# v0_1.net
KiCad netlist of a schematic drawn in EAGLE
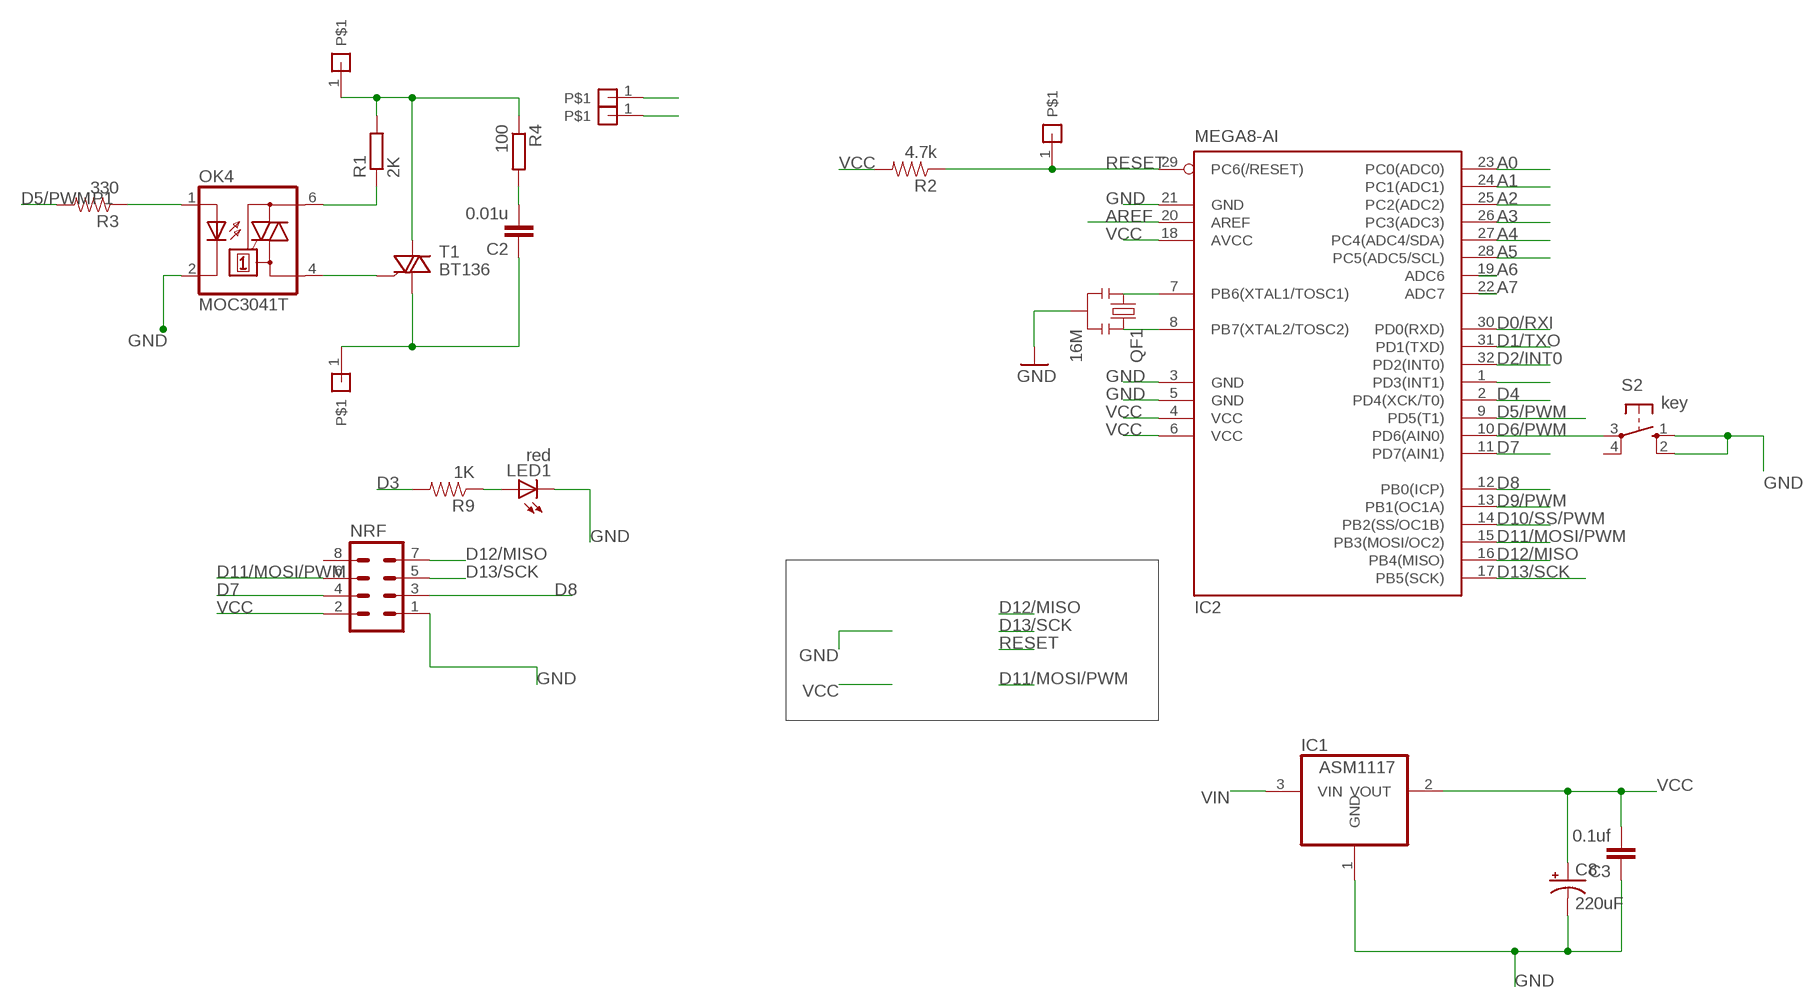
[diagram p0: schematic, sheet 1]

(export (version "E")
  (design (tool "Eeschema 10.0.6"))
  (components
    (comp (ref "C2")
      (value "0.01u")
      (footprint "eagle-import:C050-024X044")
      (libsource (lib "eagle-import") (part "C-EU050-024X044"))
    )
    (comp (ref "C3")
      (value "0.1uf")
      (footprint "eagle-import:0603-CAP")
      (libsource (lib "eagle-import") (part "CAP0603-CAP"))
    )
    (comp (ref "C8")
      (value "220uF")
      (footprint "eagle-import:EIA3528")
      (libsource (lib "eagle-import") (part "CAP_POL3528"))
    )
    (comp (ref "IC1")
      (value "ASM1117")
      (footprint "eagle-import:SOT223")
      (fields (field (name "MPN") "REG1117"))
      (libsource (lib "eagle-import") (part "REG1117"))
    )
    (comp (ref "IC2")
      (value "MEGA8-AI")
      (footprint "eagle-import:TQFP32-08")
      (fields (field (name "MPN") "ATMEGA8-16AU"))
      (libsource (lib "eagle-import") (part "MEGA8-AI"))
    )
    (comp (ref "LED1")
      (value "red")
      (footprint "eagle-import:LED3MM")
      (libsource (lib "eagle-import") (part "LED3MM"))
    )
    (comp (ref "NRF")
      (value "MA04-2")
      (footprint "eagle-import:MA04-2")
      (libsource (lib "eagle-import") (part "MA04-2"))
    )
    (comp (ref "OK4")
      (value "MOC3041T")
      (footprint "eagle-import:DIL06B")
      (libsource (lib "eagle-import") (part "MOC30T41"))
    )
    (comp (ref "QF1")
      (value "16M")
      (footprint "eagle-import:RESONATOR-PTH")
      (libsource (lib "eagle-import") (part "RESONATORPTH"))
    )
    (comp (ref "R1")
      (value "2K")
      (footprint "eagle-import:0204_7")
      (libsource (lib "eagle-import") (part "R-EU_0204/7"))
    )
    (comp (ref "R2")
      (value "4.7k")
      (footprint "eagle-import:0603-RES")
      (libsource (lib "eagle-import") (part "RESISTOR0603-RES"))
    )
    (comp (ref "R3")
      (value "330")
      (footprint "eagle-import:0603-RES")
      (libsource (lib "eagle-import") (part "RESISTOR0603-RES"))
    )
    (comp (ref "R4")
      (value "100")
      (footprint "eagle-import:0204_7")
      (libsource (lib "eagle-import") (part "R-EU_0204/7"))
    )
    (comp (ref "R9")
      (value "1K")
      (footprint "eagle-import:0603-RES")
      (libsource (lib "eagle-import") (part "RESISTOR0603-RES"))
    )
    (comp (ref "S2")
      (value "key")
      (footprint "eagle-import:B3F-10XX")
      (fields
        (field (name "MPN") "B3F-1000")
        (field (name "MPN_1") "B3F-1000")
        (field (name "OC_FARNELL") "176432")
        (field (name "OC_NEWARK") "36M3542")
      )
      (libsource (lib "eagle-import") (part "10-XX"))
    )
    (comp (ref "T1")
      (value "BT136")
      (footprint "eagle-import:TO220AB")
      (libsource (lib "eagle-import") (part "BT136"))
    )
    (comp (ref "U$1")
      (value "PIN1")
      (footprint "eagle-import:PIN1")
      (libsource (lib "eagle-import") (part "PIN1"))
    )
    (comp (ref "U$2")
      (value "PIN1")
      (footprint "eagle-import:PIN1")
      (libsource (lib "eagle-import") (part "PIN1"))
    )
    (comp (ref "U$3")
      (value "PIN1")
      (footprint "eagle-import:PIN1")
      (libsource (lib "eagle-import") (part "PIN1"))
    )
    (comp (ref "U$4")
      (value "PIN1")
      (footprint "eagle-import:PIN1")
      (libsource (lib "eagle-import") (part "PIN1"))
    )
    (comp (ref "U$5")
      (value "PIN1")
      (footprint "eagle-import:PIN1")
      (libsource (lib "eagle-import") (part "PIN1"))
    )
  )
  (nets
    (net (code "1") (name "/A0") (class "Default")
      (node (ref "IC2") (pin "23") (pinfunction "PC0(ADC0)_23") (pintype "bidirectional"))
    )
    (net (code "2") (name "/A1") (class "Default")
      (node (ref "IC2") (pin "24") (pinfunction "PC1(ADC1)_24") (pintype "bidirectional"))
    )
    (net (code "3") (name "/A2") (class "Default")
      (node (ref "IC2") (pin "25") (pinfunction "PC2(ADC2)_25") (pintype "bidirectional"))
    )
    (net (code "4") (name "/A3") (class "Default")
      (node (ref "IC2") (pin "26") (pinfunction "PC3(ADC3)_26") (pintype "bidirectional"))
    )
    (net (code "5") (name "/A4") (class "Default")
      (node (ref "IC2") (pin "27") (pinfunction "PC4(ADC4/SDA)_27") (pintype "bidirectional"))
    )
    (net (code "6") (name "/A5") (class "Default")
      (node (ref "IC2") (pin "28") (pinfunction "PC5(ADC5/SCL)_28") (pintype "bidirectional"))
    )
    (net (code "7") (name "/A6") (class "Default")
      (node (ref "IC2") (pin "19") (pinfunction "ADC6_19") (pintype "bidirectional"))
    )
    (net (code "8") (name "/A7") (class "Default")
      (node (ref "IC2") (pin "22") (pinfunction "ADC7_22") (pintype "bidirectional"))
    )
    (net (code "9") (name "/AREF") (class "Default")
      (node (ref "IC2") (pin "20") (pinfunction "AREF_20") (pintype "passive"))
    )
    (net (code "10") (name "/D0{slash}RXI") (class "Default")
      (node (ref "IC2") (pin "30") (pinfunction "PD0(RXD)_30") (pintype "bidirectional"))
    )
    (net (code "11") (name "/D1{slash}TXO") (class "Default")
      (node (ref "IC2") (pin "31") (pinfunction "PD1(TXD)_31") (pintype "bidirectional"))
    )
    (net (code "12") (name "/D2{slash}INT0") (class "Default")
      (node (ref "IC2") (pin "32") (pinfunction "PD2(INT0)_32") (pintype "bidirectional"))
    )
    (net (code "13") (name "/D3") (class "Default")
      (node (ref "IC2") (pin "1") (pinfunction "PD3(INT1)_1") (pintype "bidirectional"))
      (node (ref "R9") (pin "2") (pinfunction "2_2") (pintype "passive"))
    )
    (net (code "14") (name "/D4") (class "Default")
      (node (ref "IC2") (pin "2") (pinfunction "PD4(XCK/T0)_2") (pintype "bidirectional"))
    )
    (net (code "15") (name "/D5{slash}PWM") (class "Default")
      (node (ref "IC2") (pin "9") (pinfunction "PD5(T1)_9") (pintype "bidirectional"))
      (node (ref "R3") (pin "2") (pinfunction "2_2") (pintype "passive"))
    )
    (net (code "16") (name "/D6{slash}PWM") (class "Default")
      (node (ref "IC2") (pin "10") (pinfunction "PD6(AIN0)_10") (pintype "bidirectional"))
      (node (ref "S2") (pin "3") (pinfunction "P_3") (pintype "passive"))
    )
    (net (code "17") (name "/D7") (class "Default")
      (node (ref "IC2") (pin "11") (pinfunction "PD7(AIN1)_11") (pintype "bidirectional"))
      (node (ref "NRF") (pin "4") (pinfunction "4_4") (pintype "passive"))
    )
    (net (code "18") (name "/D8") (class "Default")
      (node (ref "IC2") (pin "12") (pinfunction "PB0(ICP)_12") (pintype "bidirectional"))
      (node (ref "NRF") (pin "3") (pinfunction "3_3") (pintype "passive"))
    )
    (net (code "19") (name "/D9{slash}PWM") (class "Default")
      (node (ref "IC2") (pin "13") (pinfunction "PB1(OC1A)_13") (pintype "bidirectional"))
    )
    (net (code "20") (name "/D10{slash}SS{slash}PWM") (class "Default")
      (node (ref "IC2") (pin "14") (pinfunction "PB2(SS/OC1B)_14") (pintype "bidirectional"))
    )
    (net (code "21") (name "/D11{slash}MOSI{slash}PWM") (class "Default")
      (node (ref "IC2") (pin "15") (pinfunction "PB3(MOSI/OC2)_15") (pintype "bidirectional"))
      (node (ref "NRF") (pin "6") (pinfunction "6_6") (pintype "passive"))
    )
    (net (code "22") (name "/D12{slash}MISO") (class "Default")
      (node (ref "IC2") (pin "16") (pinfunction "PB4(MISO)_16") (pintype "bidirectional"))
      (node (ref "NRF") (pin "7") (pinfunction "7_7") (pintype "passive"))
    )
    (net (code "23") (name "/D13{slash}SCK") (class "Default")
      (node (ref "IC2") (pin "17") (pinfunction "PB5(SCK)_17") (pintype "bidirectional"))
      (node (ref "NRF") (pin "5") (pinfunction "5_5") (pintype "passive"))
    )
    (net (code "24") (name "/P1") (class "Default")
      (node (ref "OK4") (pin "1") (pinfunction "A_1") (pintype "passive"))
      (node (ref "R3") (pin "1") (pinfunction "1_1") (pintype "passive"))
    )
    (net (code "25") (name "/RESET") (class "Default")
      (node (ref "IC2") (pin "29") (pinfunction "PC6(/RESET)_29") (pintype "bidirectional"))
      (node (ref "R2") (pin "1") (pinfunction "1_1") (pintype "passive"))
      (node (ref "U$5") (pin "1") (pinfunction "P$1_1") (pintype "bidirectional"))
    )
    (net (code "26") (name "/VCC") (class "Default")
      (node (ref "C3") (pin "2") (pinfunction "2_2") (pintype "passive"))
      (node (ref "C8") (pin "A") (pinfunction "+_A") (pintype "passive"))
      (node (ref "IC1") (pin "2") (pinfunction "VOUT_2") (pintype "output"))
      (node (ref "IC2") (pin "18") (pinfunction "AVCC_18") (pintype "power_in"))
      (node (ref "IC2") (pin "4") (pinfunction "VCC_4") (pintype "power_in"))
      (node (ref "IC2") (pin "6") (pinfunction "VCC_6") (pintype "power_in"))
      (node (ref "NRF") (pin "2") (pinfunction "2_2") (pintype "passive"))
      (node (ref "R2") (pin "2") (pinfunction "2_2") (pintype "passive"))
    )
    (net (code "27") (name "/VIN") (class "Default")
      (node (ref "IC1") (pin "3") (pinfunction "VIN_3") (pintype "input"))
      (node (ref "U$3") (pin "1") (pinfunction "P$1_1") (pintype "bidirectional"))
    )
    (net (code "28") (name "GND") (class "Default")
      (node (ref "C3") (pin "1") (pinfunction "1_1") (pintype "passive"))
      (node (ref "C8") (pin "C") (pinfunction "-_C") (pintype "passive"))
      (node (ref "IC1") (pin "1") (pinfunction "GND_1") (pintype "power_in"))
      (node (ref "IC2") (pin "21") (pinfunction "GND_21") (pintype "power_in"))
      (node (ref "IC2") (pin "3") (pinfunction "GND_3") (pintype "power_in"))
      (node (ref "IC2") (pin "5") (pinfunction "GND_5") (pintype "power_in"))
      (node (ref "LED1") (pin "K") (pinfunction "C_K") (pintype "passive"))
      (node (ref "NRF") (pin "1") (pinfunction "1_1") (pintype "passive"))
      (node (ref "OK4") (pin "2") (pinfunction "C_2") (pintype "passive"))
      (node (ref "QF1") (pin "2") (pinfunction "2_2") (pintype "passive"))
      (node (ref "S2") (pin "1") (pinfunction "S_1") (pintype "passive"))
      (node (ref "S2") (pin "2") (pinfunction "S1_2") (pintype "passive"))
      (node (ref "U$4") (pin "1") (pinfunction "P$1_1") (pintype "bidirectional"))
    )
    (net (code "29") (name "Net-(C2-Pad2)") (class "Default")
      (node (ref "C2") (pin "2") (pinfunction "2_2") (pintype "passive"))
      (node (ref "R4") (pin "2") (pinfunction "2_2") (pintype "passive"))
    )
    (net (code "30") (name "Net-(IC2-PB6(XTAL1{slash}TOSC1))") (class "Default")
      (node (ref "IC2") (pin "7") (pinfunction "PB6(XTAL1/TOSC1)_7") (pintype "bidirectional"))
      (node (ref "QF1") (pin "1") (pinfunction "1_1") (pintype "passive"))
    )
    (net (code "31") (name "Net-(IC2-PB7(XTAL2{slash}TOSC2))") (class "Default")
      (node (ref "IC2") (pin "8") (pinfunction "PB7(XTAL2/TOSC2)_8") (pintype "bidirectional"))
      (node (ref "QF1") (pin "3") (pinfunction "3_3") (pintype "passive"))
    )
    (net (code "32") (name "Net-(LED1-PadA)") (class "Default")
      (node (ref "LED1") (pin "A") (pinfunction "A_A") (pintype "passive"))
      (node (ref "R9") (pin "1") (pinfunction "1_1") (pintype "passive"))
    )
    (net (code "33") (name "Net-(OK4-A1)") (class "Default")
      (node (ref "OK4") (pin "4") (pinfunction "A1_4") (pintype "passive"))
      (node (ref "T1") (pin "3") (pinfunction "G_3") (pintype "passive"))
    )
    (net (code "34") (name "Net-(OK4-A2)") (class "Default")
      (node (ref "OK4") (pin "6") (pinfunction "A2_6") (pintype "passive"))
      (node (ref "R1") (pin "1") (pinfunction "1_1") (pintype "passive"))
    )
    (net (code "35") (name "Net-(T1-A1)") (class "Default")
      (node (ref "C2") (pin "1") (pinfunction "1_1") (pintype "passive"))
      (node (ref "T1") (pin "1") (pinfunction "A1_1") (pintype "passive"))
      (node (ref "U$1") (pin "1") (pinfunction "P$1_1") (pintype "bidirectional"))
    )
    (net (code "36") (name "Net-(T1-A2)") (class "Default")
      (node (ref "R1") (pin "2") (pinfunction "2_2") (pintype "passive"))
      (node (ref "R4") (pin "1") (pinfunction "1_1") (pintype "passive"))
      (node (ref "T1") (pin "2") (pinfunction "A2_2") (pintype "passive"))
      (node (ref "U$2") (pin "1") (pinfunction "P$1_1") (pintype "bidirectional"))
    )
    (net (code "37") (name "unconnected-(NRF-Pad8)") (class "Default")
      (node (ref "NRF") (pin "8") (pinfunction "8_8") (pintype "passive"))
    )
    (net (code "38") (name "unconnected-(S2-P1-Pad4)") (class "Default")
      (node (ref "S2") (pin "4") (pinfunction "P1_4") (pintype "passive"))
    )
  )
)
